# ATmega32_breakout_board.net
KiCad netlist of a schematic drawn in EAGLE
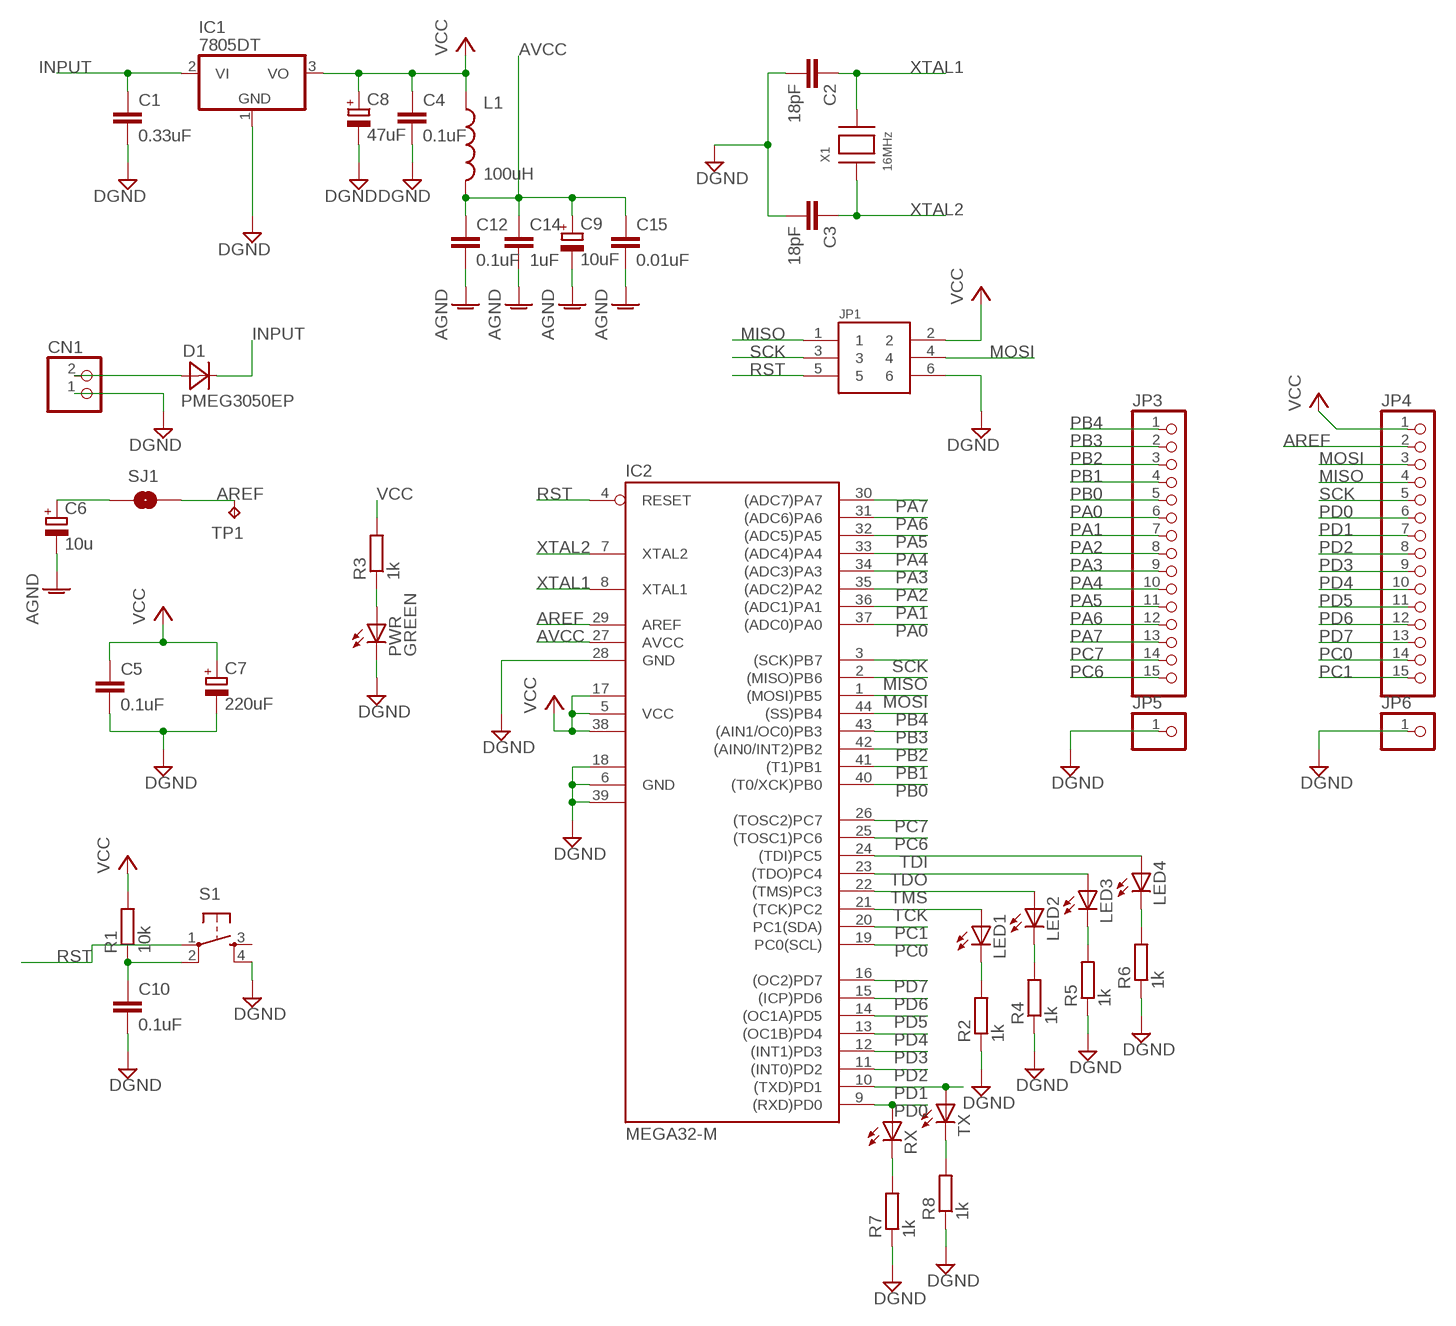
[diagram p0: schematic, sheet 1]

(export (version "E")
  (design (tool "Eeschema 10.0.6"))
  (components
    (comp (ref "C1")
      (value "0.33uF")
      (footprint "eagle-import:C0603")
      (libsource (lib "eagle-import") (part "C-EUC0603"))
    )
    (comp (ref "C2")
      (value "18pF")
      (footprint "eagle-import:C0603")
      (libsource (lib "eagle-import") (part "C-EUC0603"))
    )
    (comp (ref "C3")
      (value "18pF")
      (footprint "eagle-import:C0603")
      (libsource (lib "eagle-import") (part "C-EUC0603"))
    )
    (comp (ref "C4")
      (value "0.1uF")
      (footprint "eagle-import:C0603")
      (libsource (lib "eagle-import") (part "C-EUC0603"))
    )
    (comp (ref "C5")
      (value "0.1uF")
      (footprint "eagle-import:C0603")
      (libsource (lib "eagle-import") (part "C-EUC0603"))
    )
    (comp (ref "C6")
      (value "10u")
      (footprint "eagle-import:PANASONIC_A")
      (libsource (lib "eagle-import") (part "CPOL-EUA"))
    )
    (comp (ref "C7")
      (value "220uF")
      (footprint "eagle-import:E2,5-5")
      (libsource (lib "eagle-import") (part "resistor_CPOL-EUE2.5-5"))
    )
    (comp (ref "C8")
      (value "47uF")
      (footprint "eagle-import:E2,5-5")
      (libsource (lib "eagle-import") (part "CPOL-EUE2.5-5"))
    )
    (comp (ref "C9")
      (value "10uF")
      (footprint "eagle-import:E2-4")
      (libsource (lib "eagle-import") (part "CPOL-EUE2-4"))
    )
    (comp (ref "C10")
      (value "0.1uF")
      (footprint "eagle-import:C0603")
      (libsource (lib "eagle-import") (part "C-EUC0603"))
    )
    (comp (ref "C12")
      (value "0.1uF")
      (footprint "eagle-import:C0603")
      (libsource (lib "eagle-import") (part "C-EUC0603"))
    )
    (comp (ref "C14")
      (value "1uF")
      (footprint "eagle-import:C0603")
      (libsource (lib "eagle-import") (part "C-EUC0603"))
    )
    (comp (ref "C15")
      (value "0.01uF")
      (footprint "eagle-import:C0603")
      (libsource (lib "eagle-import") (part "C-EUC0603"))
    )
    (comp (ref "CN1")
      (value "JST_2PIN-THM-RA")
      (footprint "eagle-import:JST-PH-2-THM-RA")
      (libsource (lib "eagle-import") (part "JST_2PIN-THM-RA"))
    )
    (comp (ref "D1")
      (value "PMEG3050EP")
      (footprint "eagle-import:SMA")
      (libsource (lib "eagle-import") (part "MBRA340T3"))
    )
    (comp (ref "IC1")
      (value "7805DT")
      (footprint "eagle-import:TO252")
      (libsource (lib "eagle-import") (part "78DT05"))
    )
    (comp (ref "IC2")
      (value "MEGA32-M")
      (footprint "eagle-import:MLF44")
      (fields (field (name "MPN") "ATMEGA32-16MU"))
      (libsource (lib "eagle-import") (part "MEGA32-M"))
    )
    (comp (ref "JP1")
      (value "M03X2")
      (footprint "eagle-import:2X3-SHROUDED")
      (libsource (lib "eagle-import") (part "M03X2"))
    )
    (comp (ref "JP3")
      (value "PINHD-1X15-CB")
      (footprint "eagle-import:1X15-CB")
      (libsource (lib "eagle-import") (part "PINHD-1X15-CB"))
    )
    (comp (ref "JP4")
      (value "PINHD-1X15-CB")
      (footprint "eagle-import:1X15-CB")
      (libsource (lib "eagle-import") (part "PINHD-1X15-CB"))
    )
    (comp (ref "JP5")
      (value "PINHD-1X1CB")
      (footprint "eagle-import:1X01-CLEANBIG")
      (libsource (lib "eagle-import") (part "PINHD-1X1CB"))
    )
    (comp (ref "JP6")
      (value "PINHD-1X1CB")
      (footprint "eagle-import:1X01-CLEANBIG")
      (libsource (lib "eagle-import") (part "PINHD-1X1CB"))
    )
    (comp (ref "L1")
      (value "100uH")
      (footprint "eagle-import:0805")
      (libsource (lib "eagle-import") (part "INDUCTOR0805"))
    )
    (comp (ref "LED1")
      (value "LEDCHIPLED_0603")
      (footprint "eagle-import:CHIPLED_0603")
      (libsource (lib "eagle-import") (part "LEDCHIPLED_0603"))
    )
    (comp (ref "LED2")
      (value "LEDCHIPLED_0603")
      (footprint "eagle-import:CHIPLED_0603")
      (libsource (lib "eagle-import") (part "LEDCHIPLED_0603"))
    )
    (comp (ref "LED3")
      (value "LEDCHIPLED_0603")
      (footprint "eagle-import:CHIPLED_0603")
      (libsource (lib "eagle-import") (part "LEDCHIPLED_0603"))
    )
    (comp (ref "LED4")
      (value "LEDCHIPLED_0603")
      (footprint "eagle-import:CHIPLED_0603")
      (libsource (lib "eagle-import") (part "LEDCHIPLED_0603"))
    )
    (comp (ref "PWR")
      (value "GREEN")
      (footprint "eagle-import:CHIPLED_0805")
      (libsource (lib "eagle-import") (part "LEDCHIPLED_0805"))
    )
    (comp (ref "R1")
      (value "10k")
      (footprint "eagle-import:R0603")
      (libsource (lib "eagle-import") (part "R-EU_R0603"))
    )
    (comp (ref "R2")
      (value "1k")
      (footprint "eagle-import:R0402")
      (libsource (lib "eagle-import") (part "R-EU_R0402"))
    )
    (comp (ref "R3")
      (value "1k")
      (footprint "eagle-import:R0603")
      (libsource (lib "eagle-import") (part "R-EU_R0603"))
    )
    (comp (ref "R4")
      (value "1k")
      (footprint "eagle-import:R0402")
      (libsource (lib "eagle-import") (part "R-EU_R0402"))
    )
    (comp (ref "R5")
      (value "1k")
      (footprint "eagle-import:R0402")
      (libsource (lib "eagle-import") (part "R-EU_R0402"))
    )
    (comp (ref "R6")
      (value "1k")
      (footprint "eagle-import:R0402")
      (libsource (lib "eagle-import") (part "R-EU_R0402"))
    )
    (comp (ref "R7")
      (value "1k")
      (footprint "eagle-import:R0402")
      (libsource (lib "eagle-import") (part "R-EU_R0402"))
    )
    (comp (ref "R8")
      (value "1k")
      (footprint "eagle-import:R0402")
      (libsource (lib "eagle-import") (part "R-EU_R0402"))
    )
    (comp (ref "RX")
      (value "LEDCHIPLED_0603")
      (footprint "eagle-import:CHIPLED_0603")
      (libsource (lib "eagle-import") (part "LEDCHIPLED_0603"))
    )
    (comp (ref "S1")
      (value "TAC_SWITCHSMD")
      (footprint "eagle-import:TACTILE_SWITCH_SMD")
      (libsource (lib "eagle-import") (part "TAC_SWITCHSMD"))
    )
    (comp (ref "SJ1")
      (value "SOLDERJUMPER-OLDTRACE")
      (footprint "eagle-import:SJ_2S-TRACE")
      (libsource (lib "eagle-import") (part "SOLDERJUMPER-OLDTRACE"))
    )
    (comp (ref "TP1")
      (value "TPTP10R")
      (footprint "eagle-import:TP10R")
      (libsource (lib "eagle-import") (part "TPTP10R"))
    )
    (comp (ref "TX")
      (value "LEDCHIPLED_0603")
      (footprint "eagle-import:CHIPLED_0603")
      (libsource (lib "eagle-import") (part "LEDCHIPLED_0603"))
    )
    (comp (ref "X1")
      (value "16MHz")
      (footprint "eagle-import:NX5032")
      (libsource (lib "eagle-import") (part "XTALNX5032"))
    )
  )
  (nets
    (net (code "1") (name "/AREF") (class "Default")
      (node (ref "IC2") (pin "29") (pinfunction "AREF_29") (pintype "passive"))
      (node (ref "JP4") (pin "2") (pinfunction "2_2") (pintype "passive"))
      (node (ref "SJ1") (pin "2") (pinfunction "2_2") (pintype "passive"))
      (node (ref "TP1") (pin "TP") (pinfunction "TP_TP") (pintype "input"))
    )
    (net (code "2") (name "/AVCC") (class "Default")
      (node (ref "C12") (pin "1") (pinfunction "1_1") (pintype "passive"))
      (node (ref "C14") (pin "1") (pinfunction "1_1") (pintype "passive"))
      (node (ref "C15") (pin "1") (pinfunction "1_1") (pintype "passive"))
      (node (ref "C9") (pin "+") (pinfunction "+_+") (pintype "passive"))
      (node (ref "IC2") (pin "27") (pinfunction "AVCC_27") (pintype "power_in"))
      (node (ref "L1") (pin "2") (pinfunction "2_2") (pintype "passive"))
    )
    (net (code "3") (name "/INPUT") (class "Default")
      (node (ref "C1") (pin "1") (pinfunction "1_1") (pintype "passive"))
      (node (ref "D1") (pin "C") (pinfunction "C_C") (pintype "passive"))
      (node (ref "IC1") (pin "2") (pinfunction "VI_2") (pintype "input"))
    )
    (net (code "4") (name "/MISO") (class "Default")
      (node (ref "IC2") (pin "2") (pinfunction "(MISO)PB6_2") (pintype "bidirectional"))
      (node (ref "JP1") (pin "1") (pinfunction "1_1") (pintype "bidirectional"))
      (node (ref "JP4") (pin "4") (pinfunction "4_4") (pintype "passive"))
    )
    (net (code "5") (name "/MOSI") (class "Default")
      (node (ref "IC2") (pin "1") (pinfunction "(MOSI)PB5_1") (pintype "bidirectional"))
      (node (ref "JP1") (pin "4") (pinfunction "4_4") (pintype "bidirectional"))
      (node (ref "JP4") (pin "3") (pinfunction "3_3") (pintype "passive"))
    )
    (net (code "6") (name "/PA0") (class "Default")
      (node (ref "IC2") (pin "37") (pinfunction "(ADC0)PA0_37") (pintype "bidirectional"))
      (node (ref "JP3") (pin "6") (pinfunction "6_6") (pintype "passive"))
    )
    (net (code "7") (name "/PA1") (class "Default")
      (node (ref "IC2") (pin "36") (pinfunction "(ADC1)PA1_36") (pintype "bidirectional"))
      (node (ref "JP3") (pin "7") (pinfunction "7_7") (pintype "passive"))
    )
    (net (code "8") (name "/PA2") (class "Default")
      (node (ref "IC2") (pin "35") (pinfunction "(ADC2)PA2_35") (pintype "bidirectional"))
      (node (ref "JP3") (pin "8") (pinfunction "8_8") (pintype "passive"))
    )
    (net (code "9") (name "/PA3") (class "Default")
      (node (ref "IC2") (pin "34") (pinfunction "(ADC3)PA3_34") (pintype "bidirectional"))
      (node (ref "JP3") (pin "9") (pinfunction "9_9") (pintype "passive"))
    )
    (net (code "10") (name "/PA4") (class "Default")
      (node (ref "IC2") (pin "33") (pinfunction "(ADC4)PA4_33") (pintype "bidirectional"))
      (node (ref "JP3") (pin "10") (pinfunction "10_10") (pintype "passive"))
    )
    (net (code "11") (name "/PA5") (class "Default")
      (node (ref "IC2") (pin "32") (pinfunction "(ADC5)PA5_32") (pintype "bidirectional"))
      (node (ref "JP3") (pin "11") (pinfunction "11_11") (pintype "passive"))
    )
    (net (code "12") (name "/PA6") (class "Default")
      (node (ref "IC2") (pin "31") (pinfunction "(ADC6)PA6_31") (pintype "bidirectional"))
      (node (ref "JP3") (pin "12") (pinfunction "12_12") (pintype "passive"))
    )
    (net (code "13") (name "/PA7") (class "Default")
      (node (ref "IC2") (pin "30") (pinfunction "(ADC7)PA7_30") (pintype "bidirectional"))
      (node (ref "JP3") (pin "13") (pinfunction "13_13") (pintype "passive"))
    )
    (net (code "14") (name "/PB0") (class "Default")
      (node (ref "IC2") (pin "40") (pinfunction "(T0/XCK)PB0_40") (pintype "bidirectional"))
      (node (ref "JP3") (pin "5") (pinfunction "5_5") (pintype "passive"))
    )
    (net (code "15") (name "/PB1") (class "Default")
      (node (ref "IC2") (pin "41") (pinfunction "(T1)PB1_41") (pintype "bidirectional"))
      (node (ref "JP3") (pin "4") (pinfunction "4_4") (pintype "passive"))
    )
    (net (code "16") (name "/PB2") (class "Default")
      (node (ref "IC2") (pin "42") (pinfunction "(AIN0/INT2)PB2_42") (pintype "bidirectional"))
      (node (ref "JP3") (pin "3") (pinfunction "3_3") (pintype "passive"))
    )
    (net (code "17") (name "/PB3") (class "Default")
      (node (ref "IC2") (pin "43") (pinfunction "(AIN1/OC0)PB3_43") (pintype "bidirectional"))
      (node (ref "JP3") (pin "2") (pinfunction "2_2") (pintype "passive"))
    )
    (net (code "18") (name "/PB4") (class "Default")
      (node (ref "IC2") (pin "44") (pinfunction "(SS)PB4_44") (pintype "bidirectional"))
      (node (ref "JP3") (pin "1") (pinfunction "1_1") (pintype "passive"))
    )
    (net (code "19") (name "/PC0") (class "Default")
      (node (ref "IC2") (pin "19") (pinfunction "PC0(SCL)_19") (pintype "bidirectional"))
      (node (ref "JP4") (pin "14") (pinfunction "14_14") (pintype "passive"))
    )
    (net (code "20") (name "/PC1") (class "Default")
      (node (ref "IC2") (pin "20") (pinfunction "PC1(SDA)_20") (pintype "bidirectional"))
      (node (ref "JP4") (pin "15") (pinfunction "15_15") (pintype "passive"))
    )
    (net (code "21") (name "/PC6") (class "Default")
      (node (ref "IC2") (pin "25") (pinfunction "(TOSC1)PC6_25") (pintype "bidirectional"))
      (node (ref "JP3") (pin "15") (pinfunction "15_15") (pintype "passive"))
    )
    (net (code "22") (name "/PC7") (class "Default")
      (node (ref "IC2") (pin "26") (pinfunction "(TOSC2)PC7_26") (pintype "bidirectional"))
      (node (ref "JP3") (pin "14") (pinfunction "14_14") (pintype "passive"))
    )
    (net (code "23") (name "/PD0") (class "Default")
      (node (ref "IC2") (pin "9") (pinfunction "(RXD)PD0_9") (pintype "bidirectional"))
      (node (ref "JP4") (pin "6") (pinfunction "6_6") (pintype "passive"))
      (node (ref "RX") (pin "A") (pinfunction "A_A") (pintype "passive"))
    )
    (net (code "24") (name "/PD1") (class "Default")
      (node (ref "IC2") (pin "10") (pinfunction "(TXD)PD1_10") (pintype "bidirectional"))
      (node (ref "JP4") (pin "7") (pinfunction "7_7") (pintype "passive"))
      (node (ref "TX") (pin "A") (pinfunction "A_A") (pintype "passive"))
    )
    (net (code "25") (name "/PD2") (class "Default")
      (node (ref "IC2") (pin "11") (pinfunction "(INT0)PD2_11") (pintype "bidirectional"))
      (node (ref "JP4") (pin "8") (pinfunction "8_8") (pintype "passive"))
    )
    (net (code "26") (name "/PD3") (class "Default")
      (node (ref "IC2") (pin "12") (pinfunction "(INT1)PD3_12") (pintype "bidirectional"))
      (node (ref "JP4") (pin "9") (pinfunction "9_9") (pintype "passive"))
    )
    (net (code "27") (name "/PD4") (class "Default")
      (node (ref "IC2") (pin "13") (pinfunction "(OC1B)PD4_13") (pintype "bidirectional"))
      (node (ref "JP4") (pin "10") (pinfunction "10_10") (pintype "passive"))
    )
    (net (code "28") (name "/PD5") (class "Default")
      (node (ref "IC2") (pin "14") (pinfunction "(OC1A)PD5_14") (pintype "bidirectional"))
      (node (ref "JP4") (pin "11") (pinfunction "11_11") (pintype "passive"))
    )
    (net (code "29") (name "/PD6") (class "Default")
      (node (ref "IC2") (pin "15") (pinfunction "(ICP)PD6_15") (pintype "bidirectional"))
      (node (ref "JP4") (pin "12") (pinfunction "12_12") (pintype "passive"))
    )
    (net (code "30") (name "/PD7") (class "Default")
      (node (ref "IC2") (pin "16") (pinfunction "(OC2)PD7_16") (pintype "bidirectional"))
      (node (ref "JP4") (pin "13") (pinfunction "13_13") (pintype "passive"))
    )
    (net (code "31") (name "/RST") (class "Default")
      (node (ref "IC2") (pin "4") (pinfunction "RESET_4") (pintype "input"))
      (node (ref "JP1") (pin "5") (pinfunction "5_5") (pintype "bidirectional"))
      (node (ref "S1") (pin "1") (pinfunction "1_1") (pintype "passive"))
    )
    (net (code "32") (name "/SCK") (class "Default")
      (node (ref "IC2") (pin "3") (pinfunction "(SCK)PB7_3") (pintype "bidirectional"))
      (node (ref "JP1") (pin "3") (pinfunction "3_3") (pintype "bidirectional"))
      (node (ref "JP4") (pin "5") (pinfunction "5_5") (pintype "passive"))
    )
    (net (code "33") (name "/TCK") (class "Default")
      (node (ref "IC2") (pin "21") (pinfunction "(TCK)PC2_21") (pintype "bidirectional"))
      (node (ref "LED1") (pin "A") (pinfunction "A_A") (pintype "passive"))
    )
    (net (code "34") (name "/TDI") (class "Default")
      (node (ref "IC2") (pin "24") (pinfunction "(TDI)PC5_24") (pintype "bidirectional"))
      (node (ref "LED4") (pin "A") (pinfunction "A_A") (pintype "passive"))
    )
    (net (code "35") (name "/TDO") (class "Default")
      (node (ref "IC2") (pin "23") (pinfunction "(TDO)PC4_23") (pintype "bidirectional"))
      (node (ref "LED3") (pin "A") (pinfunction "A_A") (pintype "passive"))
    )
    (net (code "36") (name "/TMS") (class "Default")
      (node (ref "IC2") (pin "22") (pinfunction "(TMS)PC3_22") (pintype "bidirectional"))
      (node (ref "LED2") (pin "A") (pinfunction "A_A") (pintype "passive"))
    )
    (net (code "37") (name "/XTAL1") (class "Default")
      (node (ref "C2") (pin "1") (pinfunction "1_1") (pintype "passive"))
      (node (ref "IC2") (pin "8") (pinfunction "XTAL1_8") (pintype "bidirectional"))
      (node (ref "X1") (pin "P$2") (pinfunction "P$2_P$2") (pintype "bidirectional"))
    )
    (net (code "38") (name "/XTAL2") (class "Default")
      (node (ref "C3") (pin "1") (pinfunction "1_1") (pintype "passive"))
      (node (ref "IC2") (pin "7") (pinfunction "XTAL2_7") (pintype "bidirectional"))
      (node (ref "X1") (pin "P$1") (pinfunction "P$1_P$1") (pintype "bidirectional"))
    )
    (net (code "39") (name "AGND") (class "Default")
      (node (ref "C12") (pin "2") (pinfunction "2_2") (pintype "passive"))
      (node (ref "C14") (pin "2") (pinfunction "2_2") (pintype "passive"))
      (node (ref "C15") (pin "2") (pinfunction "2_2") (pintype "passive"))
      (node (ref "C6") (pin "-") (pinfunction "-_-") (pintype "passive"))
      (node (ref "C9") (pin "-") (pinfunction "-_-") (pintype "passive"))
    )
    (net (code "40") (name "DGND") (class "Default")
      (node (ref "C1") (pin "2") (pinfunction "2_2") (pintype "passive"))
      (node (ref "C10") (pin "2") (pinfunction "2_2") (pintype "passive"))
      (node (ref "C2") (pin "2") (pinfunction "2_2") (pintype "passive"))
      (node (ref "C3") (pin "2") (pinfunction "2_2") (pintype "passive"))
      (node (ref "C4") (pin "2") (pinfunction "2_2") (pintype "passive"))
      (node (ref "C5") (pin "2") (pinfunction "2_2") (pintype "passive"))
      (node (ref "C7") (pin "-") (pinfunction "-_-") (pintype "passive"))
      (node (ref "C8") (pin "-") (pinfunction "-_-") (pintype "passive"))
      (node (ref "CN1") (pin "1") (pinfunction "2_1") (pintype "passive"))
      (node (ref "IC1") (pin "1") (pinfunction "GND_1") (pintype "passive"))
      (node (ref "IC2") (pin "18") (pinfunction "GND1_18") (pintype "power_in"))
      (node (ref "IC2") (pin "28") (pinfunction "GND_28") (pintype "power_in"))
      (node (ref "IC2") (pin "39") (pinfunction "GND2_39") (pintype "power_in"))
      (node (ref "IC2") (pin "6") (pinfunction "GND_6") (pintype "power_in"))
      (node (ref "JP1") (pin "6") (pinfunction "6_6") (pintype "bidirectional"))
      (node (ref "JP5") (pin "1") (pinfunction "1_1") (pintype "passive"))
      (node (ref "JP6") (pin "1") (pinfunction "1_1") (pintype "passive"))
      (node (ref "PWR") (pin "C") (pinfunction "C_C") (pintype "passive"))
      (node (ref "R2") (pin "1") (pinfunction "1_1") (pintype "passive"))
      (node (ref "R4") (pin "1") (pinfunction "1_1") (pintype "passive"))
      (node (ref "R5") (pin "1") (pinfunction "1_1") (pintype "passive"))
      (node (ref "R6") (pin "1") (pinfunction "1_1") (pintype "passive"))
      (node (ref "R7") (pin "1") (pinfunction "1_1") (pintype "passive"))
      (node (ref "R8") (pin "1") (pinfunction "1_1") (pintype "passive"))
      (node (ref "S1") (pin "4") (pinfunction "4_4") (pintype "passive"))
    )
    (net (code "41") (name "Net-(C6-Pad+)") (class "Default")
      (node (ref "C6") (pin "+") (pinfunction "+_+") (pintype "passive"))
      (node (ref "SJ1") (pin "1") (pinfunction "1_1") (pintype "passive"))
    )
    (net (code "42") (name "Net-(C10-Pad1)") (class "Default")
      (node (ref "C10") (pin "1") (pinfunction "1_1") (pintype "passive"))
      (node (ref "R1") (pin "1") (pinfunction "1_1") (pintype "passive"))
      (node (ref "S1") (pin "2") (pinfunction "2_2") (pintype "passive"))
    )
    (net (code "43") (name "Net-(CN1-1)") (class "Default")
      (node (ref "CN1") (pin "2") (pinfunction "1_2") (pintype "passive"))
      (node (ref "D1") (pin "A") (pinfunction "A_A") (pintype "passive"))
    )
    (net (code "44") (name "Net-(LED1-PadC)") (class "Default")
      (node (ref "LED1") (pin "C") (pinfunction "C_C") (pintype "passive"))
      (node (ref "R2") (pin "2") (pinfunction "2_2") (pintype "passive"))
    )
    (net (code "45") (name "Net-(LED2-PadC)") (class "Default")
      (node (ref "LED2") (pin "C") (pinfunction "C_C") (pintype "passive"))
      (node (ref "R4") (pin "2") (pinfunction "2_2") (pintype "passive"))
    )
    (net (code "46") (name "Net-(LED3-PadC)") (class "Default")
      (node (ref "LED3") (pin "C") (pinfunction "C_C") (pintype "passive"))
      (node (ref "R5") (pin "2") (pinfunction "2_2") (pintype "passive"))
    )
    (net (code "47") (name "Net-(LED4-PadC)") (class "Default")
      (node (ref "LED4") (pin "C") (pinfunction "C_C") (pintype "passive"))
      (node (ref "R6") (pin "2") (pinfunction "2_2") (pintype "passive"))
    )
    (net (code "48") (name "Net-(PWR-PadA)") (class "Default")
      (node (ref "PWR") (pin "A") (pinfunction "A_A") (pintype "passive"))
      (node (ref "R3") (pin "1") (pinfunction "1_1") (pintype "passive"))
    )
    (net (code "49") (name "Net-(R7-Pad2)") (class "Default")
      (node (ref "R7") (pin "2") (pinfunction "2_2") (pintype "passive"))
      (node (ref "RX") (pin "C") (pinfunction "C_C") (pintype "passive"))
    )
    (net (code "50") (name "Net-(R8-Pad2)") (class "Default")
      (node (ref "R8") (pin "2") (pinfunction "2_2") (pintype "passive"))
      (node (ref "TX") (pin "C") (pinfunction "C_C") (pintype "passive"))
    )
    (net (code "51") (name "VCC") (class "Default")
      (node (ref "C4") (pin "1") (pinfunction "1_1") (pintype "passive"))
      (node (ref "C5") (pin "1") (pinfunction "1_1") (pintype "passive"))
      (node (ref "C7") (pin "+") (pinfunction "+_+") (pintype "passive"))
      (node (ref "C8") (pin "+") (pinfunction "+_+") (pintype "passive"))
      (node (ref "IC1") (pin "3") (pinfunction "VO_3") (pintype "passive"))
      (node (ref "IC2") (pin "17") (pinfunction "VCC1_17") (pintype "power_in"))
      (node (ref "IC2") (pin "38") (pinfunction "VCC2_38") (pintype "power_in"))
      (node (ref "IC2") (pin "5") (pinfunction "VCC_5") (pintype "power_in"))
      (node (ref "JP1") (pin "2") (pinfunction "2_2") (pintype "bidirectional"))
      (node (ref "JP4") (pin "1") (pinfunction "1_1") (pintype "passive"))
      (node (ref "L1") (pin "1") (pinfunction "1_1") (pintype "passive"))
      (node (ref "R1") (pin "2") (pinfunction "2_2") (pintype "passive"))
      (node (ref "R3") (pin "2") (pinfunction "2_2") (pintype "passive"))
    )
    (net (code "52") (name "unconnected-(S1-Pad3)") (class "Default")
      (node (ref "S1") (pin "3") (pinfunction "3_3") (pintype "passive"))
    )
  )
)
